# BrushlessMotorAndEncoder.net
KiCad netlist of a schematic drawn in Altium Designer
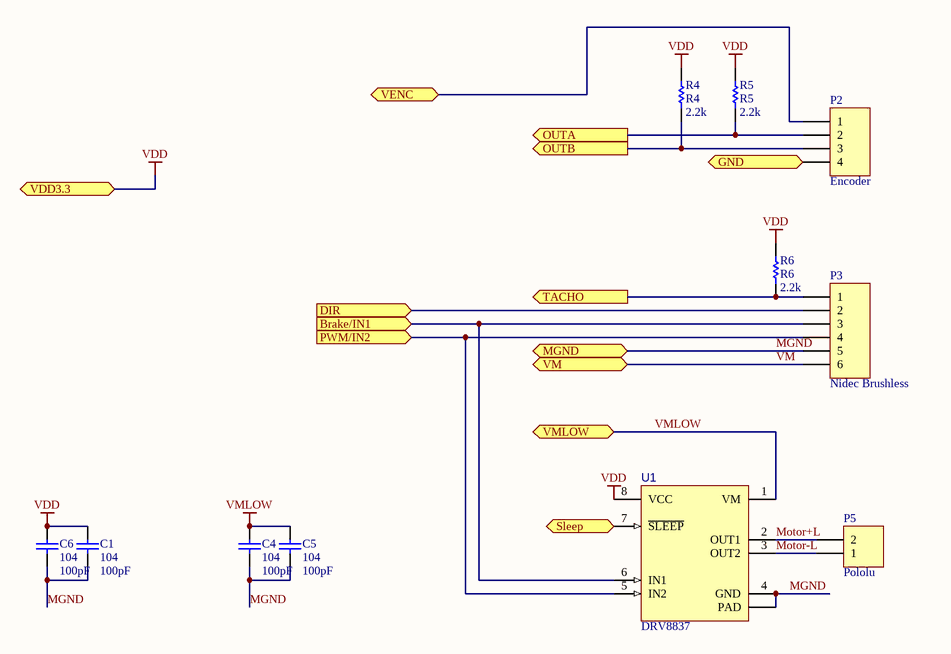
[diagram p0: BrushlessMotorAndEncoder.SchDoc]

(export (version "E")
  (design (tool "Eeschema 10.0.6"))
  (components
    (comp (ref "C1")
      (value "104")
      (footprint "CAP_0805")
      (description "Capacitor")
      (fields (field (name "ALTIUM_VALUE") "100pF") (field (name "PUBLISHER") "Altium Limited"))
      (libsource (lib "Miscellaneous Devices") (part "Cap"))
    )
    (comp (ref "C4")
      (value "104")
      (footprint "CAP_0805")
      (description "Capacitor")
      (fields (field (name "ALTIUM_VALUE") "100pF") (field (name "PUBLISHER") "Altium Limited"))
      (libsource (lib "Miscellaneous Devices") (part "Cap"))
    )
    (comp (ref "C5")
      (value "104")
      (footprint "CAP_0805")
      (description "Capacitor")
      (fields (field (name "ALTIUM_VALUE") "100pF") (field (name "PUBLISHER") "Altium Limited"))
      (libsource (lib "Miscellaneous Devices") (part "Cap"))
    )
    (comp (ref "C6")
      (value "104")
      (footprint "CAP_0805")
      (description "Capacitor")
      (fields (field (name "ALTIUM_VALUE") "100pF") (field (name "PUBLISHER") "Altium Limited"))
      (libsource (lib "Miscellaneous Devices") (part "Cap"))
    )
    (comp (ref "P2")
      (value "Encoder")
      (footprint "PH_4_PTH")
      (description "Header, 4-Pin")
      (fields (field (name "PUBLISHER") "Altium Limited"))
      (libsource (lib "Miscellaneous Connectors") (part "Header 4"))
    )
    (comp (ref "P3")
      (value "Nidec Brushless")
      (footprint "PH_6_PTH")
      (description "Header, 6-Pin")
      (fields (field (name "PUBLISHER") "Altium Limited"))
      (libsource (lib "Miscellaneous Connectors") (part "Header 6"))
    )
    (comp (ref "P5")
      (value "Pololu")
      (footprint "PH_2_PTH")
      (description "Header, 2-Pin")
      (fields (field (name "PUBLISHER") "Altium Limited"))
      (libsource (lib "Miscellaneous Connectors") (part "Header 2"))
    )
    (comp (ref "R4")
      (value "R4")
      (footprint "RES_0805")
      (description "Resistor")
      (fields (field (name "ALTIUM_VALUE") "2.2k") (field (name "PUBLISHER") "Altium Limited"))
      (libsource (lib "Miscellaneous Devices") (part "Res1"))
    )
    (comp (ref "R5")
      (value "R5")
      (footprint "RES_0805")
      (description "Resistor")
      (fields (field (name "ALTIUM_VALUE") "2.2k") (field (name "PUBLISHER") "Altium Limited"))
      (libsource (lib "Miscellaneous Devices") (part "Res1"))
    )
    (comp (ref "R6")
      (value "R6")
      (footprint "RES_0805")
      (description "Resistor")
      (fields (field (name "ALTIUM_VALUE") "2.2k") (field (name "PUBLISHER") "Altium Limited"))
      (libsource (lib "Miscellaneous Devices") (part "Res1"))
    )
    (comp (ref "U1")
      (value "DRV8837")
      (footprint "DSG0008A")
      (description "LOW-VOLTAGE H-BRIDGE IC, DSG0008A")
      (fields
        (field (name "PARTNUMBER") "DRV8837DSG")
        (field (name "MANUFACTURER") "Texas Instruments")
        (field (name "SYMBOLCREATOR") "a0411947")
        (field (name "PUBLISHER") "Texas Instruments")
      )
      (libsource (lib "SmartMouse2016") (part "DRV8837DSG"))
    )
  )
  (nets
    (net (code "1") (name "/Brake{slash}IN1") (class "Default")
      (node (ref "P3") (pin "3") (pinfunction "3_3") (pintype "passive"))
      (node (ref "U1") (pin "6") (pinfunction "IN1_6") (pintype "input"))
    )
    (net (code "2") (name "/DIR") (class "Default")
      (node (ref "P3") (pin "2") (pinfunction "2_2") (pintype "passive"))
    )
    (net (code "3") (name "/GND") (class "Default")
      (node (ref "P2") (pin "4") (pinfunction "4_4") (pintype "passive"))
    )
    (net (code "4") (name "/MGND") (class "Default")
      (node (ref "C1") (pin "1") (pinfunction "1_1") (pintype "passive"))
      (node (ref "C4") (pin "1") (pinfunction "1_1") (pintype "passive"))
      (node (ref "C5") (pin "1") (pinfunction "1_1") (pintype "passive"))
      (node (ref "C6") (pin "1") (pinfunction "1_1") (pintype "passive"))
      (node (ref "P3") (pin "5") (pinfunction "5_5") (pintype "passive"))
      (node (ref "U1") (pin "4") (pinfunction "GND_4") (pintype "power_in"))
      (node (ref "U1") (pin "9") (pinfunction "PAD_9") (pintype "power_in"))
    )
    (net (code "5") (name "/Motor+L") (class "Default")
      (node (ref "P5") (pin "2") (pinfunction "2_2") (pintype "passive"))
      (node (ref "U1") (pin "2") (pinfunction "OUT1_2") (pintype "power_in"))
    )
    (net (code "6") (name "/Motor-L") (class "Default")
      (node (ref "P5") (pin "1") (pinfunction "1_1") (pintype "passive"))
      (node (ref "U1") (pin "3") (pinfunction "OUT2_3") (pintype "power_in"))
    )
    (net (code "7") (name "/OUTA") (class "Default")
      (node (ref "P2") (pin "2") (pinfunction "2_2") (pintype "passive"))
      (node (ref "R5") (pin "1") (pinfunction "1_1") (pintype "passive"))
    )
    (net (code "8") (name "/OUTB") (class "Default")
      (node (ref "P2") (pin "3") (pinfunction "3_3") (pintype "passive"))
      (node (ref "R4") (pin "1") (pinfunction "1_1") (pintype "passive"))
    )
    (net (code "9") (name "/PWM{slash}IN2") (class "Default")
      (node (ref "P3") (pin "4") (pinfunction "4_4") (pintype "passive"))
      (node (ref "U1") (pin "5") (pinfunction "IN2_5") (pintype "input"))
    )
    (net (code "10") (name "/Sleep") (class "Default")
      (node (ref "U1") (pin "7") (pinfunction "SLEEP_7") (pintype "input"))
    )
    (net (code "11") (name "/TACHO") (class "Default")
      (node (ref "P3") (pin "1") (pinfunction "1_1") (pintype "passive"))
      (node (ref "R6") (pin "1") (pinfunction "1_1") (pintype "passive"))
    )
    (net (code "12") (name "/VENC") (class "Default")
      (node (ref "P2") (pin "1") (pinfunction "1_1") (pintype "passive"))
    )
    (net (code "13") (name "/VM") (class "Default")
      (node (ref "P3") (pin "6") (pinfunction "6_6") (pintype "passive"))
    )
    (net (code "14") (name "VDD") (class "Default")
      (node (ref "C1") (pin "2") (pinfunction "2_2") (pintype "passive"))
      (node (ref "C6") (pin "2") (pinfunction "2_2") (pintype "passive"))
      (node (ref "R4") (pin "2") (pinfunction "2_2") (pintype "passive"))
      (node (ref "R5") (pin "2") (pinfunction "2_2") (pintype "passive"))
      (node (ref "R6") (pin "2") (pinfunction "2_2") (pintype "passive"))
      (node (ref "U1") (pin "8") (pinfunction "VCC_8") (pintype "power_in"))
    )
    (net (code "15") (name "VMLOW") (class "Default")
      (node (ref "C4") (pin "2") (pinfunction "2_2") (pintype "passive"))
      (node (ref "C5") (pin "2") (pinfunction "2_2") (pintype "passive"))
      (node (ref "U1") (pin "1") (pinfunction "VM_1") (pintype "power_in"))
    )
  )
)
